# ArmDebuger_3-7_STLink_V2.net
KiCad netlist of a schematic drawn in Altium Designer
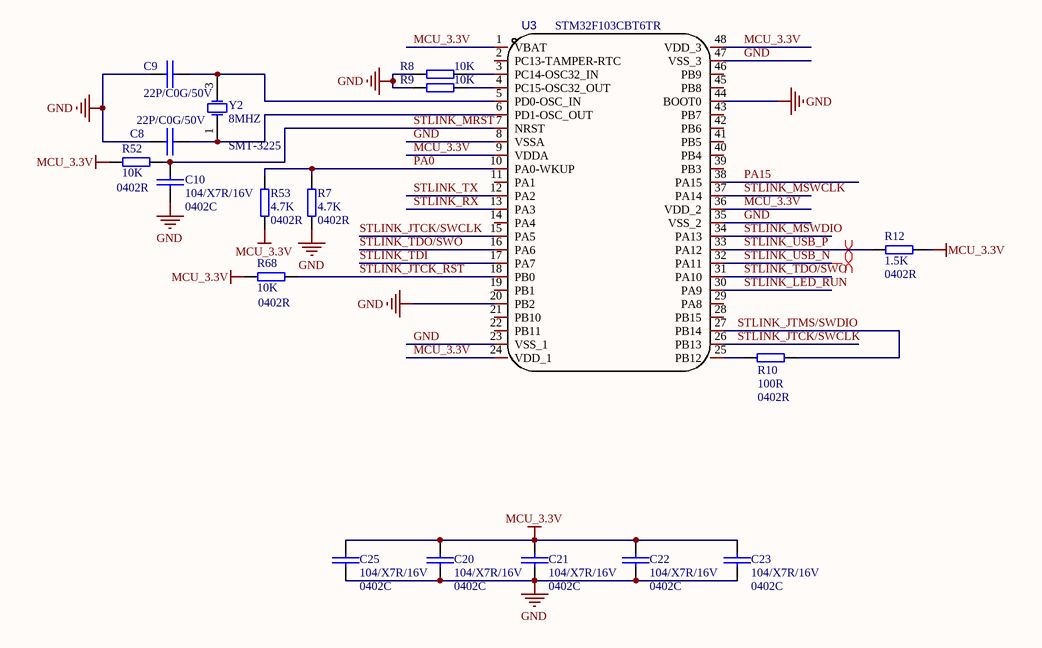
[diagram p0: ArmDebuger(3-7)STLink_V2.SchDoc]

(export (version "E")
  (design (tool "Eeschema 10.0.6"))
  (components
    (comp (ref "C8") (value "22P/C0G/50V") (footprint "0402C-SMD-M") (libsource (lib "*") (part "CAP")))
    (comp (ref "C9") (value "22P/C0G/50V") (footprint "0402C-SMD-M") (libsource (lib "*") (part "CAP")))
    (comp (ref "C10")
      (value "104/X7R/16V")
      (footprint "0402C-SMD-M")
      (fields (field (name "FP") "0402C"))
      (libsource (lib "*") (part "CAP"))
    )
    (comp (ref "C20")
      (value "104/X7R/16V")
      (footprint "0402C-SMD-M")
      (fields (field (name "FP") "0402C"))
      (libsource (lib "*") (part "CAP"))
    )
    (comp (ref "C21")
      (value "104/X7R/16V")
      (footprint "0402C-SMD-M")
      (fields (field (name "FP") "0402C"))
      (libsource (lib "*") (part "CAP"))
    )
    (comp (ref "C22")
      (value "104/X7R/16V")
      (footprint "0402C-SMD-M")
      (fields (field (name "FP") "0402C"))
      (libsource (lib "*") (part "CAP"))
    )
    (comp (ref "C23")
      (value "104/X7R/16V")
      (footprint "0402C-SMD-M")
      (fields (field (name "FP") "0402C"))
      (libsource (lib "*") (part "CAP"))
    )
    (comp (ref "C25")
      (value "104/X7R/16V")
      (footprint "0402C-SMD-M")
      (fields (field (name "FP") "0402C"))
      (libsource (lib "*") (part "CAP"))
    )
    (comp (ref "R7")
      (value "4.7K")
      (footprint "0402R-SMD-M")
      (fields (field (name "FP") "0402R"))
      (libsource (lib "*") (part "RES"))
    )
    (comp (ref "R8") (value "10K") (footprint "0402R-SMD-M") (libsource (lib "*") (part "RES")))
    (comp (ref "R9") (value "10K") (footprint "0402R-SMD-M") (libsource (lib "*") (part "RES")))
    (comp (ref "R10")
      (value "100R")
      (footprint "0402R-SMD-M")
      (fields (field (name "FP") "0402R"))
      (libsource (lib "*") (part "RES"))
    )
    (comp (ref "R12")
      (value "1.5K")
      (footprint "0402R-SMD-M")
      (fields (field (name "FP") "0402R"))
      (libsource (lib "*") (part "RES"))
    )
    (comp (ref "R52")
      (value "10K")
      (footprint "0402R-SMD-M")
      (fields (field (name "FP") "0402R"))
      (libsource (lib "*") (part "RES"))
    )
    (comp (ref "R53")
      (value "4.7K")
      (footprint "0402R-SMD-M")
      (fields (field (name "FP") "0402R"))
      (libsource (lib "*") (part "RES"))
    )
    (comp (ref "R68")
      (value "10K")
      (footprint "0402R-SMD-M")
      (fields (field (name "FP") "0402R"))
      (libsource (lib "*") (part "RES"))
    )
    (comp (ref "U3")
      (value "STM32F103CBT6TR")
      (footprint "LQFP48_L")
      (libsource (lib "altium-import") (part "root_0_STM32F103C8T6TR_"))
    )
    (comp (ref "Y2")
      (value "8MHZ")
      (footprint "CRYSTAL-SMT-3225")
      (description "贴片晶振")
      (fields (field (name "FP") "SMT-3225"))
      (libsource (lib "CrystalOscillator") (part "SMD-3225_4P  25MHZ 12PF 10PPM"))
    )
  )
  (nets
    (net (code "1") (name "/PA0") (class "Default")
      (node (ref "R53") (pin "2") (pinfunction "2_2") (pintype "passive"))
      (node (ref "R7") (pin "2") (pinfunction "2_2") (pintype "passive"))
      (node (ref "U3") (pin "10") (pinfunction "PA0-WKUP_10") (pintype "passive"))
    )
    (net (code "2") (name "/PA15") (class "Default")
      (node (ref "U3") (pin "38") (pinfunction "PA15_38") (pintype "passive"))
    )
    (net (code "3") (name "/STLINK_JTCK_RST") (class "Default")
      (node (ref "R68") (pin "2") (pinfunction "2_2") (pintype "passive"))
      (node (ref "U3") (pin "18") (pinfunction "PB0_18") (pintype "passive"))
    )
    (net (code "4") (name "/STLINK_JTCK{slash}SWCLK") (class "Default")
      (node (ref "U3") (pin "15") (pinfunction "PA5_15") (pintype "passive"))
      (node (ref "U3") (pin "26") (pinfunction "PB13_26") (pintype "passive"))
    )
    (net (code "5") (name "/STLINK_JTMS{slash}SWDIO") (class "Default")
      (node (ref "R10") (pin "2") (pinfunction "2_2") (pintype "passive"))
      (node (ref "U3") (pin "27") (pinfunction "PB14_27") (pintype "passive"))
    )
    (net (code "6") (name "/STLINK_LED_RUN") (class "Default")
      (node (ref "U3") (pin "30") (pinfunction "PA9_30") (pintype "passive"))
    )
    (net (code "7") (name "/STLINK_MRST") (class "Default")
      (node (ref "C10") (pin "2") (pinfunction "1_2") (pintype "passive"))
      (node (ref "R52") (pin "2") (pinfunction "2_2") (pintype "passive"))
      (node (ref "U3") (pin "7") (pinfunction "NRST_7") (pintype "passive"))
    )
    (net (code "8") (name "/STLINK_MSWCLK") (class "Default")
      (node (ref "U3") (pin "37") (pinfunction "PA14_37") (pintype "passive"))
    )
    (net (code "9") (name "/STLINK_MSWDIO") (class "Default")
      (node (ref "U3") (pin "34") (pinfunction "PA13_34") (pintype "passive"))
    )
    (net (code "10") (name "/STLINK_RX") (class "Default")
      (node (ref "U3") (pin "13") (pinfunction "PA3_13") (pintype "passive"))
    )
    (net (code "11") (name "/STLINK_TDI") (class "Default")
      (node (ref "U3") (pin "17") (pinfunction "PA7_17") (pintype "passive"))
    )
    (net (code "12") (name "/STLINK_TDO{slash}SWO") (class "Default")
      (node (ref "U3") (pin "16") (pinfunction "PA6_16") (pintype "passive"))
      (node (ref "U3") (pin "31") (pinfunction "PA10_31") (pintype "passive"))
    )
    (net (code "13") (name "/STLINK_TX") (class "Default")
      (node (ref "U3") (pin "12") (pinfunction "PA2_12") (pintype "passive"))
    )
    (net (code "14") (name "/STLINK_USB_N") (class "Default")
      (node (ref "U3") (pin "32") (pinfunction "PA11_32") (pintype "passive"))
    )
    (net (code "15") (name "/STLINK_USB_P") (class "Default")
      (node (ref "R12") (pin "2") (pinfunction "2_2") (pintype "passive"))
      (node (ref "U3") (pin "33") (pinfunction "PA12_33") (pintype "passive"))
    )
    (net (code "16") (name "GND") (class "Default")
      (node (ref "C10") (pin "1") (pinfunction "1_1") (pintype "passive"))
      (node (ref "C20") (pin "1") (pinfunction "1_1") (pintype "passive"))
      (node (ref "C21") (pin "1") (pinfunction "1_1") (pintype "passive"))
      (node (ref "C22") (pin "1") (pinfunction "1_1") (pintype "passive"))
      (node (ref "C23") (pin "1") (pinfunction "1_1") (pintype "passive"))
      (node (ref "C25") (pin "1") (pinfunction "1_1") (pintype "passive"))
      (node (ref "C8") (pin "1") (pinfunction "1_1") (pintype "passive"))
      (node (ref "C9") (pin "1") (pinfunction "1_1") (pintype "passive"))
      (node (ref "R7") (pin "1") (pinfunction "1_1") (pintype "passive"))
      (node (ref "R8") (pin "1") (pinfunction "1_1") (pintype "passive"))
      (node (ref "R9") (pin "1") (pinfunction "1_1") (pintype "passive"))
      (node (ref "U3") (pin "20") (pinfunction "PB2_20") (pintype "passive"))
      (node (ref "U3") (pin "23") (pinfunction "VSS_1_23") (pintype "passive"))
      (node (ref "U3") (pin "35") (pinfunction "VSS_2_35") (pintype "passive"))
      (node (ref "U3") (pin "44") (pinfunction "BOOT0_44") (pintype "passive"))
      (node (ref "U3") (pin "47") (pinfunction "VSS_3_47") (pintype "passive"))
      (node (ref "U3") (pin "8") (pinfunction "VSSA_8") (pintype "passive"))
    )
    (net (code "17") (name "MCU_3.3V") (class "Default")
      (node (ref "C20") (pin "2") (pinfunction "1_2") (pintype "passive"))
      (node (ref "C21") (pin "2") (pinfunction "1_2") (pintype "passive"))
      (node (ref "C22") (pin "2") (pinfunction "1_2") (pintype "passive"))
      (node (ref "C23") (pin "2") (pinfunction "1_2") (pintype "passive"))
      (node (ref "C25") (pin "2") (pinfunction "1_2") (pintype "passive"))
      (node (ref "R12") (pin "1") (pinfunction "1_1") (pintype "passive"))
      (node (ref "R52") (pin "1") (pinfunction "1_1") (pintype "passive"))
      (node (ref "R53") (pin "1") (pinfunction "1_1") (pintype "passive"))
      (node (ref "R68") (pin "1") (pinfunction "1_1") (pintype "passive"))
      (node (ref "U3") (pin "1") (pinfunction "VBAT_1") (pintype "passive"))
      (node (ref "U3") (pin "24") (pinfunction "VDD_1_24") (pintype "passive"))
      (node (ref "U3") (pin "36") (pinfunction "VDD_2_36") (pintype "passive"))
      (node (ref "U3") (pin "48") (pinfunction "VDD_3_48") (pintype "passive"))
      (node (ref "U3") (pin "9") (pinfunction "VDDA_9") (pintype "passive"))
    )
    (net (code "18") (name "Net-(U3-PB12)") (class "Default")
      (node (ref "R10") (pin "1") (pinfunction "1_1") (pintype "passive"))
      (node (ref "U3") (pin "25") (pinfunction "PB12_25") (pintype "passive"))
    )
    (net (code "19") (name "Net-(U3-PC14-OSC32_IN)") (class "Default")
      (node (ref "R8") (pin "2") (pinfunction "2_2") (pintype "passive"))
      (node (ref "U3") (pin "3") (pinfunction "PC14-OSC32_IN_3") (pintype "passive"))
    )
    (net (code "20") (name "Net-(U3-PC15-OSC32_OUT)") (class "Default")
      (node (ref "R9") (pin "2") (pinfunction "2_2") (pintype "passive"))
      (node (ref "U3") (pin "4") (pinfunction "PC15-OSC32_OUT_4") (pintype "passive"))
    )
    (net (code "21") (name "Net-(U3-PD0-OSC_IN)") (class "Default")
      (node (ref "C9") (pin "2") (pinfunction "1_2") (pintype "passive"))
      (node (ref "U3") (pin "5") (pinfunction "PD0-OSC_IN_5") (pintype "passive"))
      (node (ref "Y2") (pin "3") (pinfunction "OSC2_3") (pintype "passive"))
    )
    (net (code "22") (name "Net-(U3-PD1-OSC_OUT)") (class "Default")
      (node (ref "C8") (pin "2") (pinfunction "1_2") (pintype "passive"))
      (node (ref "U3") (pin "6") (pinfunction "PD1-OSC_OUT_6") (pintype "passive"))
      (node (ref "Y2") (pin "1") (pinfunction "OSC1_1") (pintype "passive"))
    )
    (net (code "23") (name "unconnected-(U3-PA1-Pad11)") (class "Default")
      (node (ref "U3") (pin "11") (pinfunction "PA1_11") (pintype "passive"))
    )
    (net (code "24") (name "unconnected-(U3-PA4-Pad14)") (class "Default")
      (node (ref "U3") (pin "14") (pinfunction "PA4_14") (pintype "passive"))
    )
    (net (code "25") (name "unconnected-(U3-PA8-Pad29)") (class "Default")
      (node (ref "U3") (pin "29") (pinfunction "PA8_29") (pintype "passive"))
    )
    (net (code "26") (name "unconnected-(U3-PB1-Pad19)") (class "Default")
      (node (ref "U3") (pin "19") (pinfunction "PB1_19") (pintype "passive"))
    )
    (net (code "27") (name "unconnected-(U3-PB3-Pad39)") (class "Default")
      (node (ref "U3") (pin "39") (pinfunction "PB3_39") (pintype "passive"))
    )
    (net (code "28") (name "unconnected-(U3-PB4-Pad40)") (class "Default")
      (node (ref "U3") (pin "40") (pinfunction "PB4_40") (pintype "passive"))
    )
    (net (code "29") (name "unconnected-(U3-PB5-Pad41)") (class "Default")
      (node (ref "U3") (pin "41") (pinfunction "PB5_41") (pintype "passive"))
    )
    (net (code "30") (name "unconnected-(U3-PB6-Pad42)") (class "Default")
      (node (ref "U3") (pin "42") (pinfunction "PB6_42") (pintype "passive"))
    )
    (net (code "31") (name "unconnected-(U3-PB7-Pad43)") (class "Default")
      (node (ref "U3") (pin "43") (pinfunction "PB7_43") (pintype "passive"))
    )
    (net (code "32") (name "unconnected-(U3-PB8-Pad45)") (class "Default")
      (node (ref "U3") (pin "45") (pinfunction "PB8_45") (pintype "passive"))
    )
    (net (code "33") (name "unconnected-(U3-PB9-Pad46)") (class "Default")
      (node (ref "U3") (pin "46") (pinfunction "PB9_46") (pintype "passive"))
    )
    (net (code "34") (name "unconnected-(U3-PB10-Pad21)") (class "Default")
      (node (ref "U3") (pin "21") (pinfunction "PB10_21") (pintype "passive"))
    )
    (net (code "35") (name "unconnected-(U3-PB11-Pad22)") (class "Default")
      (node (ref "U3") (pin "22") (pinfunction "PB11_22") (pintype "passive"))
    )
    (net (code "36") (name "unconnected-(U3-PB15-Pad28)") (class "Default")
      (node (ref "U3") (pin "28") (pinfunction "PB15_28") (pintype "passive"))
    )
    (net (code "37") (name "unconnected-(U3-PC13-TAMPER-RTC-Pad2)") (class "Default")
      (node (ref "U3") (pin "2") (pinfunction "PC13-TAMPER-RTC_2") (pintype "passive"))
    )
  )
)
